# BUTTON.net
KiCad netlist of a schematic drawn in Altium Designer
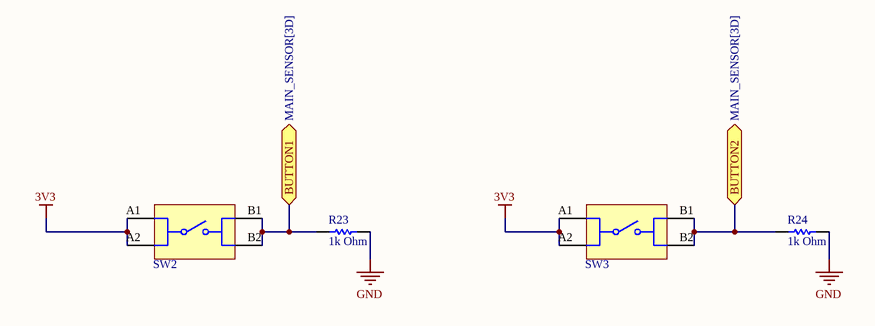
[diagram p0: BUTTON.SchDoc]

(export (version "E")
  (design (tool "Eeschema 10.0.6"))
  (components
    (comp (ref "R23")
      (value "1k Ohm")
      (footprint "resistor_0603")
      (description "RES, size 0603, 1 KOhm, 1/4 W")
      (libsource (lib "Altium_Resistor") (part "0006031021"))
    )
    (comp (ref "R24")
      (value "1k Ohm")
      (footprint "resistor_0603")
      (description "RES, size 0603, 1 KOhm, 1/4 W")
      (libsource (lib "Altium_Resistor") (part "0006031021"))
    )
    (comp (ref "SW2")
      (value "430152043826")
      (footprint "WS-TASV_L6W6H4.3_4301x20438x6")
      (description "WS-TASV SMT Tact Switch, L6 x W6 x H4.3mm, 260g, SPST-NO, 12V, 50mA")
      (fields (field (name "MANUFACTURER") "Wurth Elektronik"))
      (libsource (lib "Altium_Button") (part "430152043826"))
    )
    (comp (ref "SW3")
      (value "430152043826")
      (footprint "WS-TASV_L6W6H4.3_4301x20438x6")
      (description "WS-TASV SMT Tact Switch, L6 x W6 x H4.3mm, 260g, SPST-NO, 12V, 50mA")
      (fields (field (name "MANUFACTURER") "Wurth Elektronik"))
      (libsource (lib "Altium_Button") (part "430152043826"))
    )
  )
  (nets
    (net (code "1") (name "/BUTTON1") (class "Default")
      (node (ref "R23") (pin "1") (pinfunction "1_1") (pintype "passive"))
      (node (ref "SW2") (pin "B1") (pinfunction "B1_B1") (pintype "passive"))
      (node (ref "SW2") (pin "B2") (pinfunction "B2_B2") (pintype "passive"))
    )
    (net (code "2") (name "/BUTTON2") (class "Default")
      (node (ref "R24") (pin "1") (pinfunction "1_1") (pintype "passive"))
      (node (ref "SW3") (pin "B1") (pinfunction "B1_B1") (pintype "passive"))
      (node (ref "SW3") (pin "B2") (pinfunction "B2_B2") (pintype "passive"))
    )
    (net (code "3") (name "3V3") (class "Default")
      (node (ref "SW2") (pin "A1") (pinfunction "A1_A1") (pintype "passive"))
      (node (ref "SW2") (pin "A2") (pinfunction "A2_A2") (pintype "passive"))
      (node (ref "SW3") (pin "A1") (pinfunction "A1_A1") (pintype "passive"))
      (node (ref "SW3") (pin "A2") (pinfunction "A2_A2") (pintype "passive"))
    )
    (net (code "4") (name "GND") (class "Default")
      (node (ref "R23") (pin "2") (pinfunction "2_2") (pintype "passive"))
      (node (ref "R24") (pin "2") (pinfunction "2_2") (pintype "passive"))
    )
  )
)
